# PowCarbinBoard_Connect.net
KiCad netlist of a schematic drawn in Altium Designer
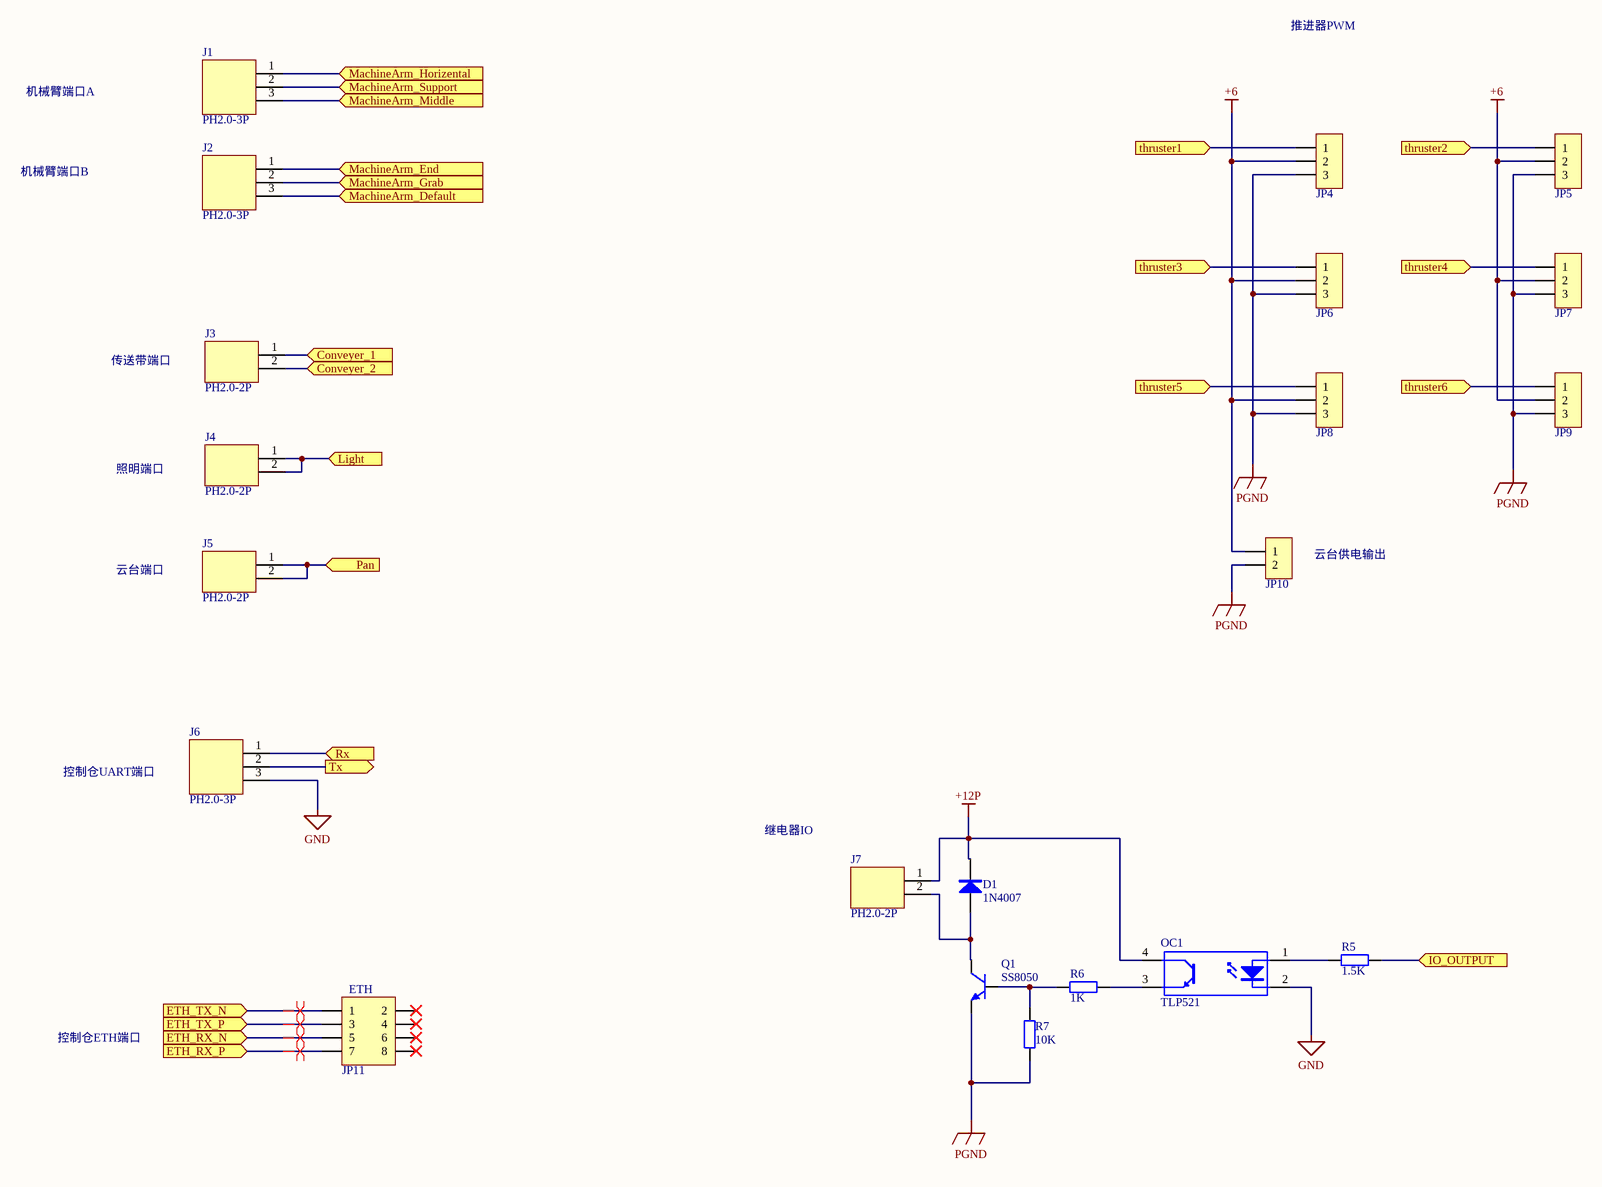
[diagram p0: PowCarbinBoard_Connect.SchDoc]

(export (version "E")
  (design (tool "Eeschema 10.0.6"))
  (components
    (comp (ref "D1")
      (value "1N4007")
      (footprint "SOD-123")
      (description "整流二极管")
      (fields (field (name "版权归属") "源创客"))
      (libsource (lib "8.1   - 二极管-整流桥") (part "1N4007"))
    )
    (comp (ref "J1") (value "PH2.0-3P") (footprint "PH2.0-3P") (libsource (lib "PH") (part "PH2.0-3P")))
    (comp (ref "J2") (value "PH2.0-3P") (footprint "PH2.0-3P") (libsource (lib "PH") (part "PH2.0-3P")))
    (comp (ref "J3") (value "PH2.0-2P") (footprint "PH2.0-2P") (libsource (lib "PH") (part "PH2.0-2P")))
    (comp (ref "J4") (value "PH2.0-2P") (footprint "PH2.0-2P") (libsource (lib "PH") (part "PH2.0-2P")))
    (comp (ref "J5") (value "PH2.0-2P") (footprint "PH2.0-2P") (libsource (lib "PH") (part "PH2.0-2P")))
    (comp (ref "J6") (value "PH2.0-3P") (footprint "PH2.0-3P") (libsource (lib "PH") (part "PH2.0-3P")))
    (comp (ref "J7") (value "PH2.0-2P") (footprint "PH2.0-2P") (libsource (lib "PH") (part "PH2.0-2P")))
    (comp (ref "JP4")
      (value "HDR-1X3")
      (footprint "HDR2.54-LI-3P")
      (description "3P接插件")
      (fields (field (name "版权归属") "源创客"))
      (libsource (lib "4.5   - 接插件-脚距2.54") (part "Header 3"))
    )
    (comp (ref "JP5")
      (value "HDR-1X3")
      (footprint "HDR2.54-LI-3P")
      (description "3P接插件")
      (fields (field (name "版权归属") "源创客"))
      (libsource (lib "4.5   - 接插件-脚距2.54") (part "Header 3"))
    )
    (comp (ref "JP6")
      (value "HDR-1X3")
      (footprint "HDR2.54-LI-3P")
      (description "3P接插件")
      (fields (field (name "版权归属") "源创客"))
      (libsource (lib "4.5   - 接插件-脚距2.54") (part "Header 3"))
    )
    (comp (ref "JP7")
      (value "HDR-1X3")
      (footprint "HDR2.54-LI-3P")
      (description "3P接插件")
      (fields (field (name "版权归属") "源创客"))
      (libsource (lib "4.5   - 接插件-脚距2.54") (part "Header 3"))
    )
    (comp (ref "JP8")
      (value "HDR-1X3")
      (footprint "HDR2.54-LI-3P")
      (description "3P接插件")
      (fields (field (name "版权归属") "源创客"))
      (libsource (lib "4.5   - 接插件-脚距2.54") (part "Header 3"))
    )
    (comp (ref "JP9")
      (value "HDR-1X3")
      (footprint "HDR2.54-LI-3P")
      (description "3P接插件")
      (fields (field (name "版权归属") "源创客"))
      (libsource (lib "4.5   - 接插件-脚距2.54") (part "Header 3"))
    )
    (comp (ref "JP10")
      (value "HDR-1X2")
      (footprint "KF128-5.08-2P")
      (description "2P接插件")
      (fields (field (name "版权归属") "源创客"))
      (libsource (lib "4.10 - 接插件-脚距5.08") (part "Header 2"))
    )
    (comp (ref "JP11")
      (value "ETH")
      (footprint "PHB2.0-LI-2x4P")
      (description "4*2P接插件")
      (fields (field (name "版权归属") "源创客"))
      (libsource (lib "4.4   - 接插件-脚距2.0") (part "Header 4X2"))
    )
    (comp (ref "OC1")
      (value "TLP521")
      (footprint "DIP_TLP521")
      (description "开关光耦")
      (libsource (lib "光电隔离器") (part "TLP521"))
    )
    (comp (ref "Q1")
      (value "SS8050")
      (footprint "SOT23-3N")
      (description "高频放大-NPN型")
      (fields (field (name "版权归属") "源创客"))
      (libsource (lib "6.2   - 三极管") (part "8050-SMD"))
    )
    (comp (ref "R5")
      (value "1.5K")
      (footprint "0603_R")
      (description "贴片电阻")
      (libsource (lib "") (part "0603 10KΩ (1002) 1%_1"))
    )
    (comp (ref "R6")
      (value "1K")
      (footprint "0603_R")
      (description "贴片电阻")
      (libsource (lib "") (part "0603 10KΩ (1002) 1%_2"))
    )
    (comp (ref "R7")
      (value "10K")
      (footprint "0603_R")
      (description "贴片电阻")
      (libsource (lib "Miscellaneous Devices LC") (part "0603 10KΩ (1002) 1%"))
    )
  )
  (nets
    (net (code "1") (name "+6") (class "Default")
      (node (ref "JP10") (pin "1") (pinfunction "1_1") (pintype "passive"))
      (node (ref "JP4") (pin "2") (pinfunction "2_2") (pintype "passive"))
      (node (ref "JP5") (pin "2") (pinfunction "2_2") (pintype "passive"))
      (node (ref "JP6") (pin "2") (pinfunction "2_2") (pintype "passive"))
      (node (ref "JP7") (pin "2") (pinfunction "2_2") (pintype "passive"))
      (node (ref "JP8") (pin "2") (pinfunction "2_2") (pintype "passive"))
      (node (ref "JP9") (pin "2") (pinfunction "2_2") (pintype "passive"))
    )
    (net (code "2") (name "+12P") (class "Default")
      (node (ref "D1") (pin "2") (pinfunction "K_2") (pintype "passive"))
      (node (ref "J7") (pin "1") (pinfunction "1_1") (pintype "passive"))
      (node (ref "OC1") (pin "4") (pinfunction "C_4") (pintype "passive"))
    )
    (net (code "3") (name "/Conveyer_1") (class "Default")
      (node (ref "J3") (pin "1") (pinfunction "1_1") (pintype "passive"))
    )
    (net (code "4") (name "/Conveyer_2") (class "Default")
      (node (ref "J3") (pin "2") (pinfunction "2_2") (pintype "passive"))
    )
    (net (code "5") (name "/ETH_RX_N") (class "Default")
      (node (ref "JP11") (pin "5") (pinfunction "5_5") (pintype "passive"))
    )
    (net (code "6") (name "/ETH_RX_P") (class "Default")
      (node (ref "JP11") (pin "7") (pinfunction "7_7") (pintype "passive"))
    )
    (net (code "7") (name "/ETH_TX_N") (class "Default")
      (node (ref "JP11") (pin "1") (pinfunction "1_1") (pintype "passive"))
    )
    (net (code "8") (name "/ETH_TX_P") (class "Default")
      (node (ref "JP11") (pin "3") (pinfunction "3_3") (pintype "passive"))
    )
    (net (code "9") (name "/IO_OUTPUT") (class "Default")
      (node (ref "R5") (pin "2") (pinfunction "2_2") (pintype "passive"))
    )
    (net (code "10") (name "/Light") (class "Default")
      (node (ref "J4") (pin "1") (pinfunction "1_1") (pintype "passive"))
      (node (ref "J4") (pin "2") (pinfunction "2_2") (pintype "passive"))
    )
    (net (code "11") (name "/MachineArm_Default") (class "Default")
      (node (ref "J2") (pin "3") (pinfunction "3_3") (pintype "passive"))
    )
    (net (code "12") (name "/MachineArm_End") (class "Default")
      (node (ref "J2") (pin "1") (pinfunction "1_1") (pintype "passive"))
    )
    (net (code "13") (name "/MachineArm_Grab") (class "Default")
      (node (ref "J2") (pin "2") (pinfunction "2_2") (pintype "passive"))
    )
    (net (code "14") (name "/MachineArm_Horizental") (class "Default")
      (node (ref "J1") (pin "1") (pinfunction "1_1") (pintype "passive"))
    )
    (net (code "15") (name "/MachineArm_Middle") (class "Default")
      (node (ref "J1") (pin "3") (pinfunction "3_3") (pintype "passive"))
    )
    (net (code "16") (name "/MachineArm_Support") (class "Default")
      (node (ref "J1") (pin "2") (pinfunction "2_2") (pintype "passive"))
    )
    (net (code "17") (name "/Pan") (class "Default")
      (node (ref "J5") (pin "1") (pinfunction "1_1") (pintype "passive"))
      (node (ref "J5") (pin "2") (pinfunction "2_2") (pintype "passive"))
    )
    (net (code "18") (name "/Rx") (class "Default")
      (node (ref "J6") (pin "1") (pinfunction "1_1") (pintype "passive"))
    )
    (net (code "19") (name "/Tx") (class "Default")
      (node (ref "J6") (pin "2") (pinfunction "2_2") (pintype "passive"))
    )
    (net (code "20") (name "/thruster1") (class "Default")
      (node (ref "JP4") (pin "1") (pinfunction "1_1") (pintype "passive"))
    )
    (net (code "21") (name "/thruster2") (class "Default")
      (node (ref "JP5") (pin "1") (pinfunction "1_1") (pintype "passive"))
    )
    (net (code "22") (name "/thruster3") (class "Default")
      (node (ref "JP6") (pin "1") (pinfunction "1_1") (pintype "passive"))
    )
    (net (code "23") (name "/thruster4") (class "Default")
      (node (ref "JP7") (pin "1") (pinfunction "1_1") (pintype "passive"))
    )
    (net (code "24") (name "/thruster5") (class "Default")
      (node (ref "JP8") (pin "1") (pinfunction "1_1") (pintype "passive"))
    )
    (net (code "25") (name "/thruster6") (class "Default")
      (node (ref "JP9") (pin "1") (pinfunction "1_1") (pintype "passive"))
    )
    (net (code "26") (name "GND") (class "Default")
      (node (ref "J6") (pin "3") (pinfunction "3_3") (pintype "passive"))
      (node (ref "OC1") (pin "2") (pinfunction "K_2") (pintype "passive"))
    )
    (net (code "27") (name "Net-(D1-A)") (class "Default")
      (node (ref "D1") (pin "1") (pinfunction "A_1") (pintype "passive"))
      (node (ref "J7") (pin "2") (pinfunction "2_2") (pintype "passive"))
      (node (ref "Q1") (pin "3") (pinfunction "C_3") (pintype "passive"))
    )
    (net (code "28") (name "Net-(OC1-A)") (class "Default")
      (node (ref "OC1") (pin "1") (pinfunction "A_1") (pintype "passive"))
      (node (ref "R5") (pin "1") (pinfunction "1_1") (pintype "passive"))
    )
    (net (code "29") (name "Net-(OC1-E)") (class "Default")
      (node (ref "OC1") (pin "3") (pinfunction "E_3") (pintype "passive"))
      (node (ref "R6") (pin "1") (pinfunction "1_1") (pintype "passive"))
    )
    (net (code "30") (name "Net-(Q1-B)") (class "Default")
      (node (ref "Q1") (pin "1") (pinfunction "B_1") (pintype "passive"))
      (node (ref "R6") (pin "2") (pinfunction "2_2") (pintype "passive"))
      (node (ref "R7") (pin "2") (pinfunction "2_2") (pintype "passive"))
    )
    (net (code "31") (name "PGND") (class "Default")
      (node (ref "JP10") (pin "2") (pinfunction "2_2") (pintype "passive"))
      (node (ref "JP4") (pin "3") (pinfunction "3_3") (pintype "passive"))
      (node (ref "JP5") (pin "3") (pinfunction "3_3") (pintype "passive"))
      (node (ref "JP6") (pin "3") (pinfunction "3_3") (pintype "passive"))
      (node (ref "JP7") (pin "3") (pinfunction "3_3") (pintype "passive"))
      (node (ref "JP8") (pin "3") (pinfunction "3_3") (pintype "passive"))
      (node (ref "JP9") (pin "3") (pinfunction "3_3") (pintype "passive"))
      (node (ref "Q1") (pin "2") (pinfunction "E_2") (pintype "passive"))
      (node (ref "R7") (pin "1") (pinfunction "1_1") (pintype "passive"))
    )
    (net (code "32") (name "unconnected-(JP11-Pad2)") (class "Default")
      (node (ref "JP11") (pin "2") (pinfunction "2_2") (pintype "passive+no_connect"))
    )
    (net (code "33") (name "unconnected-(JP11-Pad4)") (class "Default")
      (node (ref "JP11") (pin "4") (pinfunction "4_4") (pintype "passive+no_connect"))
    )
    (net (code "34") (name "unconnected-(JP11-Pad6)") (class "Default")
      (node (ref "JP11") (pin "6") (pinfunction "6_6") (pintype "passive+no_connect"))
    )
    (net (code "35") (name "unconnected-(JP11-Pad8)") (class "Default")
      (node (ref "JP11") (pin "8") (pinfunction "8_8") (pintype "passive+no_connect"))
    )
  )
)
